# Friedman_BeOd.net
KiCad netlist of a schematic drawn in EAGLE
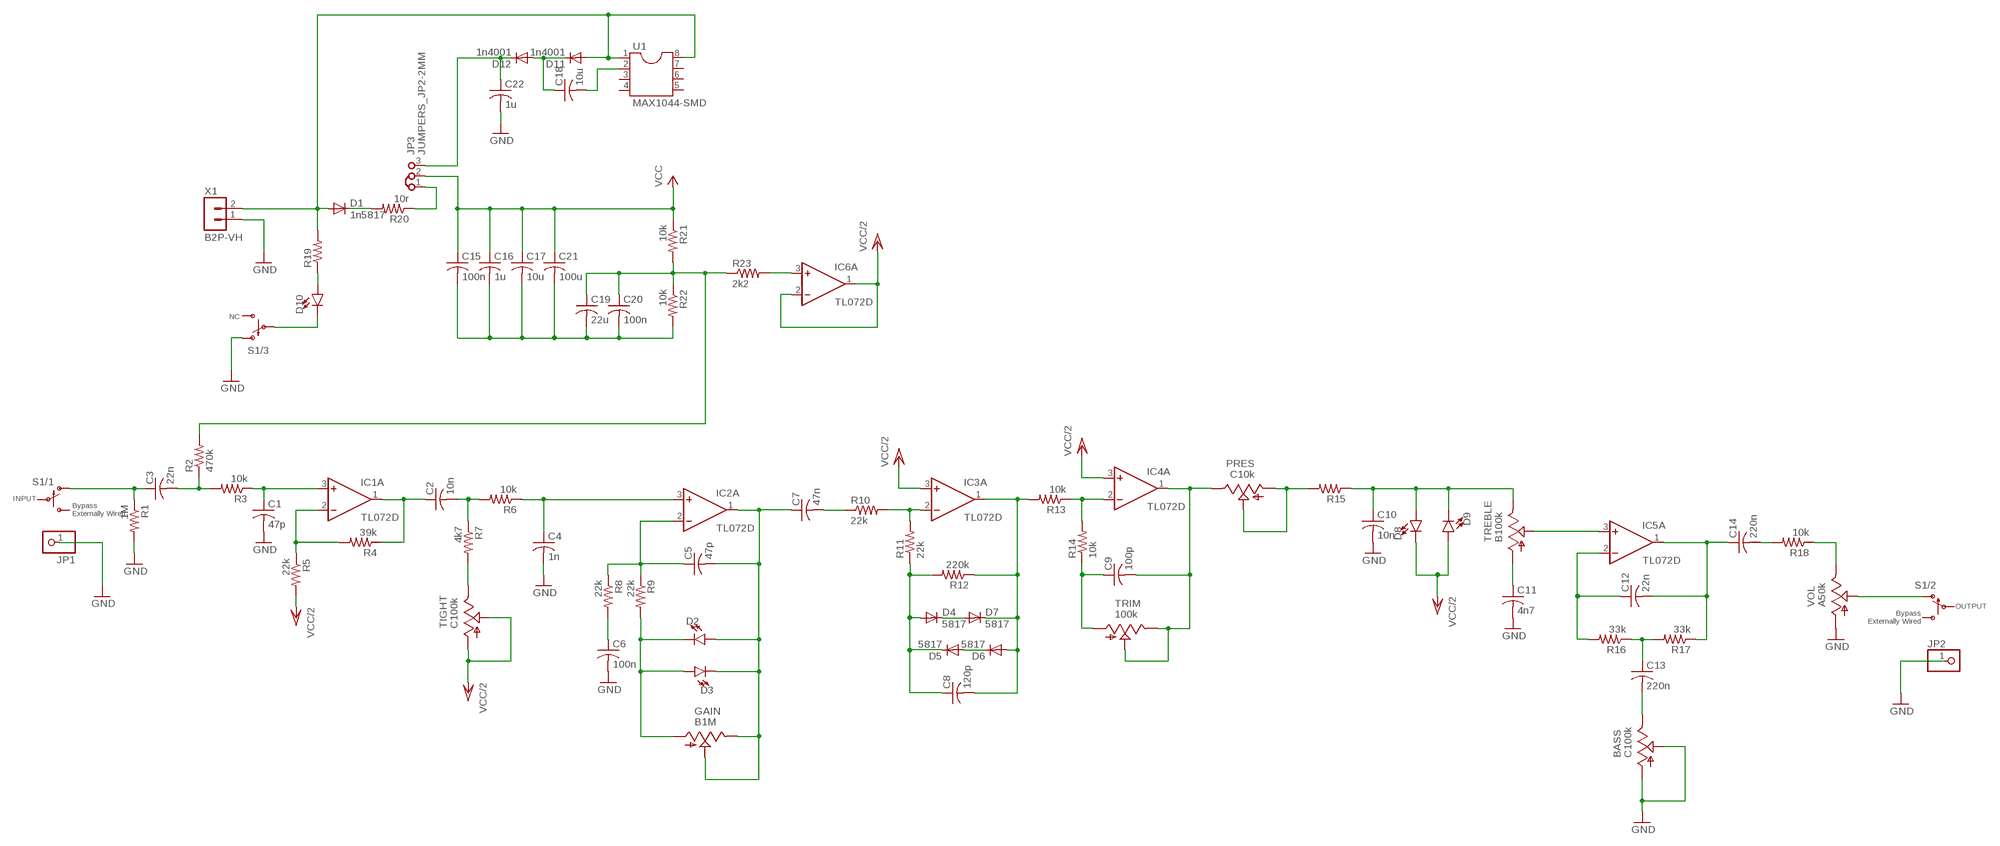
[diagram p0: schematic, sheet 1]

(export (version "E")
  (design (tool "Eeschema 10.0.6"))
  (components
    (comp (ref "BASS")
      (value "C100k")
      (footprint "eagle-import:61300311121")
      (libsource (lib "eagle-import") (part "POT"))
    )
    (comp (ref "C1")
      (value "47p")
      (footprint "eagle-import:C0603")
      (libsource (lib "eagle-import") (part "C-USC0603"))
    )
    (comp (ref "C2")
      (value "10n")
      (footprint "eagle-import:C0603")
      (libsource (lib "eagle-import") (part "C-USC0603"))
    )
    (comp (ref "C3")
      (value "22n")
      (footprint "eagle-import:C0603")
      (libsource (lib "eagle-import") (part "C-USC0603"))
    )
    (comp (ref "C4")
      (value "1n")
      (footprint "eagle-import:C0603")
      (libsource (lib "eagle-import") (part "C-USC0603"))
    )
    (comp (ref "C5")
      (value "47p")
      (footprint "eagle-import:C0603")
      (libsource (lib "eagle-import") (part "C-USC0603"))
    )
    (comp (ref "C6")
      (value "100n")
      (footprint "eagle-import:C0603")
      (libsource (lib "eagle-import") (part "C-USC0603"))
    )
    (comp (ref "C7")
      (value "47n")
      (footprint "eagle-import:C0603")
      (libsource (lib "eagle-import") (part "C-USC0603"))
    )
    (comp (ref "C8")
      (value "120p")
      (footprint "eagle-import:C0603")
      (libsource (lib "eagle-import") (part "C-USC0603"))
    )
    (comp (ref "C9")
      (value "100p")
      (footprint "eagle-import:C0603")
      (libsource (lib "eagle-import") (part "C-USC0603"))
    )
    (comp (ref "C10")
      (value "10n")
      (footprint "eagle-import:C0603")
      (libsource (lib "eagle-import") (part "C-USC0603"))
    )
    (comp (ref "C11")
      (value "4n7")
      (footprint "eagle-import:C0603")
      (libsource (lib "eagle-import") (part "C-USC0603"))
    )
    (comp (ref "C12")
      (value "22n")
      (footprint "eagle-import:C0603")
      (libsource (lib "eagle-import") (part "C-USC0603"))
    )
    (comp (ref "C13")
      (value "220n")
      (footprint "eagle-import:C0603")
      (libsource (lib "eagle-import") (part "C-USC0603"))
    )
    (comp (ref "C14")
      (value "220n")
      (footprint "eagle-import:C0603")
      (libsource (lib "eagle-import") (part "C-USC0603"))
    )
    (comp (ref "C15")
      (value "100n")
      (footprint "eagle-import:C0603")
      (libsource (lib "eagle-import") (part "C-USC0603"))
    )
    (comp (ref "C16")
      (value "1u")
      (footprint "eagle-import:C0603")
      (libsource (lib "eagle-import") (part "C-USC0603"))
    )
    (comp (ref "C17")
      (value "10u")
      (footprint "eagle-import:C0603")
      (libsource (lib "eagle-import") (part "C-USC0603"))
    )
    (comp (ref "C18")
      (value "10u")
      (footprint "eagle-import:C0603")
      (libsource (lib "eagle-import") (part "C-USC0603"))
    )
    (comp (ref "C19")
      (value "22u")
      (footprint "eagle-import:C0603")
      (libsource (lib "eagle-import") (part "C-USC0603"))
    )
    (comp (ref "C20")
      (value "100n")
      (footprint "eagle-import:C0603")
      (libsource (lib "eagle-import") (part "C-USC0603"))
    )
    (comp (ref "C21")
      (value "100u")
      (footprint "eagle-import:C075-032X103")
      (libsource (lib "eagle-import") (part "C-US075-032X103"))
    )
    (comp (ref "C22")
      (value "1u")
      (footprint "eagle-import:C0603")
      (libsource (lib "eagle-import") (part "C-USC0603"))
    )
    (comp (ref "D1")
      (value "1n5817")
      (footprint "eagle-import:DO41-10")
      (libsource (lib "eagle-import") (part "1N4004"))
    )
    (comp (ref "D2")
      (value "LED3MM")
      (footprint "eagle-import:LED_3MM")
      (libsource (lib "eagle-import") (part "LED3MM"))
    )
    (comp (ref "D3")
      (value "LED3MM")
      (footprint "eagle-import:LED_3MM")
      (libsource (lib "eagle-import") (part "LED3MM"))
    )
    (comp (ref "D4")
      (value "5817")
      (footprint "eagle-import:DO41-10")
      (libsource (lib "eagle-import") (part "1N4004"))
    )
    (comp (ref "D5")
      (value "5817")
      (footprint "eagle-import:DO41-10")
      (libsource (lib "eagle-import") (part "1N4004"))
    )
    (comp (ref "D6")
      (value "5817")
      (footprint "eagle-import:DO41-10")
      (libsource (lib "eagle-import") (part "1N4004"))
    )
    (comp (ref "D7")
      (value "5817")
      (footprint "eagle-import:DO41-10")
      (libsource (lib "eagle-import") (part "1N4004"))
    )
    (comp (ref "D8")
      (value "LED3MM")
      (footprint "eagle-import:LED_3MM")
      (libsource (lib "eagle-import") (part "LED3MM"))
    )
    (comp (ref "D9")
      (value "LED3MM")
      (footprint "eagle-import:LED_3MM")
      (libsource (lib "eagle-import") (part "LED3MM"))
    )
    (comp (ref "D10")
      (value "LED3MM")
      (footprint "eagle-import:LED_3MM")
      (libsource (lib "eagle-import") (part "LED3MM"))
    )
    (comp (ref "D11")
      (value "1n4001")
      (footprint "eagle-import:DO41-10")
      (libsource (lib "eagle-import") (part "1N4004"))
    )
    (comp (ref "D12")
      (value "1n4001")
      (footprint "eagle-import:DO41-10")
      (libsource (lib "eagle-import") (part "1N4004"))
    )
    (comp (ref "GAIN")
      (value "B1M")
      (footprint "eagle-import:61300311121")
      (libsource (lib "eagle-import") (part "POT"))
    )
    (comp (ref "IC1")
      (value "TL072D")
      (footprint "eagle-import:SO08")
      (libsource (lib "eagle-import") (part "TL072D"))
    )
    (comp (ref "IC2")
      (value "TL072D")
      (footprint "eagle-import:SO08")
      (libsource (lib "eagle-import") (part "TL072D"))
    )
    (comp (ref "IC3")
      (value "TL072D")
      (footprint "eagle-import:SO08")
      (libsource (lib "eagle-import") (part "TL072D"))
    )
    (comp (ref "IC4")
      (value "TL072D")
      (footprint "eagle-import:SO08")
      (libsource (lib "eagle-import") (part "TL072D"))
    )
    (comp (ref "IC5")
      (value "TL072D")
      (footprint "eagle-import:SO08")
      (libsource (lib "eagle-import") (part "TL072D"))
    )
    (comp (ref "IC6")
      (value "TL072D")
      (footprint "eagle-import:SO08")
      (libsource (lib "eagle-import") (part "TL072D"))
    )
    (comp (ref "JP1")
      (value "PINHD-1X1")
      (footprint "eagle-import:1X01")
      (libsource (lib "eagle-import") (part "PINHD-1X1"))
    )
    (comp (ref "JP2")
      (value "PINHD-1X1")
      (footprint "eagle-import:1X01")
      (libsource (lib "eagle-import") (part "PINHD-1X1"))
    )
    (comp (ref "JP3")
      (value "JUMPERS_JP2-2MM")
      (footprint "eagle-import:JUMPERS_JP2-2MM")
      (libsource (lib "eagle-import") (part "JUMPERS_JP2-2MM"))
    )
    (comp (ref "PRES")
      (value "C10k")
      (footprint "eagle-import:61300311121")
      (libsource (lib "eagle-import") (part "POT"))
    )
    (comp (ref "R1")
      (value "1M")
      (footprint "eagle-import:R0603")
      (libsource (lib "eagle-import") (part "R-US_R0603"))
    )
    (comp (ref "R2")
      (value "470k")
      (footprint "eagle-import:R0603")
      (libsource (lib "eagle-import") (part "R-US_R0603"))
    )
    (comp (ref "R3")
      (value "10k")
      (footprint "eagle-import:R0603")
      (libsource (lib "eagle-import") (part "R-US_R0603"))
    )
    (comp (ref "R4")
      (value "39k")
      (footprint "eagle-import:R0603")
      (libsource (lib "eagle-import") (part "R-US_R0603"))
    )
    (comp (ref "R5")
      (value "22k")
      (footprint "eagle-import:R0603")
      (libsource (lib "eagle-import") (part "R-US_R0603"))
    )
    (comp (ref "R6")
      (value "10k")
      (footprint "eagle-import:R0603")
      (libsource (lib "eagle-import") (part "R-US_R0603"))
    )
    (comp (ref "R7")
      (value "4k7")
      (footprint "eagle-import:R0603")
      (libsource (lib "eagle-import") (part "R-US_R0603"))
    )
    (comp (ref "R8")
      (value "22k")
      (footprint "eagle-import:R0603")
      (libsource (lib "eagle-import") (part "R-US_R0603"))
    )
    (comp (ref "R9")
      (value "22k")
      (footprint "eagle-import:R0603")
      (libsource (lib "eagle-import") (part "R-US_R0603"))
    )
    (comp (ref "R10")
      (value "22k")
      (footprint "eagle-import:R0603")
      (libsource (lib "eagle-import") (part "R-US_R0603"))
    )
    (comp (ref "R11")
      (value "22k")
      (footprint "eagle-import:R0603")
      (libsource (lib "eagle-import") (part "R-US_R0603"))
    )
    (comp (ref "R12")
      (value "220k")
      (footprint "eagle-import:R0603")
      (libsource (lib "eagle-import") (part "R-US_R0603"))
    )
    (comp (ref "R13")
      (value "10k")
      (footprint "eagle-import:R0603")
      (libsource (lib "eagle-import") (part "R-US_R0603"))
    )
    (comp (ref "R14")
      (value "10k")
      (footprint "eagle-import:R0603")
      (libsource (lib "eagle-import") (part "R-US_R0603"))
    )
    (comp (ref "R15")
      (value "R-US_R0603")
      (footprint "eagle-import:R0603")
      (libsource (lib "eagle-import") (part "R-US_R0603"))
    )
    (comp (ref "R16")
      (value "33k")
      (footprint "eagle-import:R0603")
      (libsource (lib "eagle-import") (part "R-US_R0603"))
    )
    (comp (ref "R17")
      (value "33k")
      (footprint "eagle-import:R0603")
      (libsource (lib "eagle-import") (part "R-US_R0603"))
    )
    (comp (ref "R18")
      (value "10k")
      (footprint "eagle-import:R0603")
      (libsource (lib "eagle-import") (part "R-US_R0603"))
    )
    (comp (ref "R19")
      (value "R-US_R0603")
      (footprint "eagle-import:R0603")
      (libsource (lib "eagle-import") (part "R-US_R0603"))
    )
    (comp (ref "R20")
      (value "10r")
      (footprint "eagle-import:R0603")
      (libsource (lib "eagle-import") (part "R-US_R0603"))
    )
    (comp (ref "R21")
      (value "10k")
      (footprint "eagle-import:R0603")
      (libsource (lib "eagle-import") (part "R-US_R0603"))
    )
    (comp (ref "R22")
      (value "10k")
      (footprint "eagle-import:R0603")
      (libsource (lib "eagle-import") (part "R-US_R0603"))
    )
    (comp (ref "R23")
      (value "2k2")
      (footprint "eagle-import:R0603")
      (libsource (lib "eagle-import") (part "R-US_R0603"))
    )
    (comp (ref "S1")
      (value "SWITCH-3DPT-INLINE-BREAKOUT-BYPASS")
      (footprint "eagle-import:1X04")
      (libsource (lib "eagle-import") (part "SWITCH-3DPT-INLINE-BREAKOUT-BYPASS"))
    )
    (comp (ref "TIGHT")
      (value "C100k")
      (footprint "eagle-import:61300311121")
      (libsource (lib "eagle-import") (part "POT"))
    )
    (comp (ref "TREBLE")
      (value "B100k")
      (footprint "eagle-import:61300311121")
      (libsource (lib "eagle-import") (part "POT"))
    )
    (comp (ref "TRIM")
      (value "100k")
      (footprint "eagle-import:61300311121")
      (libsource (lib "eagle-import") (part "POT"))
    )
    (comp (ref "U1")
      (value "MAX1044-SMD")
      (footprint "eagle-import:SO-08")
      (libsource (lib "eagle-import") (part "MAX1044-SMD"))
    )
    (comp (ref "VOL")
      (value "A50k")
      (footprint "eagle-import:61300311121")
      (libsource (lib "eagle-import") (part "POT"))
    )
    (comp (ref "X1")
      (value "B2P-VH")
      (footprint "eagle-import:B2P-VH")
      (libsource (lib "eagle-import") (part "B2P-VH"))
    )
  )
  (nets
    (net (code "1") (name "GND") (class "Default")
      (node (ref "BASS") (pin "1") (pinfunction "LEFT_1") (pintype "passive"))
      (node (ref "BASS") (pin "2") (pinfunction "WIPER_2") (pintype "passive"))
      (node (ref "C1") (pin "2") (pinfunction "2_2") (pintype "passive"))
      (node (ref "C10") (pin "2") (pinfunction "2_2") (pintype "passive"))
      (node (ref "C11") (pin "2") (pinfunction "2_2") (pintype "passive"))
      (node (ref "C22") (pin "2") (pinfunction "2_2") (pintype "passive"))
      (node (ref "C4") (pin "2") (pinfunction "2_2") (pintype "passive"))
      (node (ref "C6") (pin "2") (pinfunction "2_2") (pintype "passive"))
      (node (ref "JP1") (pin "1") (pinfunction "1_1") (pintype "passive"))
      (node (ref "JP2") (pin "1") (pinfunction "1_1") (pintype "passive"))
      (node (ref "R1") (pin "2") (pinfunction "2_2") (pintype "passive"))
      (node (ref "S1") (pin "4") (pinfunction "NORMALLY-ON_4") (pintype "passive"))
      (node (ref "VOL") (pin "1") (pinfunction "LEFT_1") (pintype "passive"))
      (node (ref "X1") (pin "1") (pinfunction "1_1") (pintype "passive"))
    )
    (net (code "2") (name "Net-(BASS-RIGHT)") (class "Default")
      (node (ref "BASS") (pin "3") (pinfunction "RIGHT_3") (pintype "passive"))
      (node (ref "C13") (pin "2") (pinfunction "2_2") (pintype "passive"))
    )
    (net (code "3") (name "Net-(C2-Pad2)") (class "Default")
      (node (ref "C2") (pin "2") (pinfunction "2_2") (pintype "passive"))
      (node (ref "R6") (pin "2") (pinfunction "2_2") (pintype "passive"))
      (node (ref "R7") (pin "1") (pinfunction "1_1") (pintype "passive"))
    )
    (net (code "4") (name "Net-(C3-Pad2)") (class "Default")
      (node (ref "C3") (pin "2") (pinfunction "2_2") (pintype "passive"))
      (node (ref "R2") (pin "1") (pinfunction "1_1") (pintype "passive"))
      (node (ref "R3") (pin "2") (pinfunction "2_2") (pintype "passive"))
    )
    (net (code "5") (name "Net-(C6-Pad1)") (class "Default")
      (node (ref "C6") (pin "1") (pinfunction "1_1") (pintype "passive"))
      (node (ref "R8") (pin "2") (pinfunction "2_2") (pintype "passive"))
    )
    (net (code "6") (name "Net-(C7-Pad2)") (class "Default")
      (node (ref "C7") (pin "2") (pinfunction "2_2") (pintype "passive"))
      (node (ref "R10") (pin "1") (pinfunction "1_1") (pintype "passive"))
    )
    (net (code "7") (name "Net-(C8-Pad1)") (class "Default")
      (node (ref "C8") (pin "1") (pinfunction "1_1") (pintype "passive"))
      (node (ref "D4") (pin "A") (pinfunction "A_A") (pintype "passive"))
      (node (ref "D5") (pin "C") (pinfunction "C_C") (pintype "passive"))
      (node (ref "R11") (pin "1") (pinfunction "1_1") (pintype "passive"))
      (node (ref "R12") (pin "2") (pinfunction "2_2") (pintype "passive"))
    )
    (net (code "8") (name "Net-(C13-Pad1)") (class "Default")
      (node (ref "C13") (pin "1") (pinfunction "1_1") (pintype "passive"))
      (node (ref "R16") (pin "1") (pinfunction "1_1") (pintype "passive"))
      (node (ref "R17") (pin "2") (pinfunction "2_2") (pintype "passive"))
    )
    (net (code "9") (name "Net-(C14-Pad2)") (class "Default")
      (node (ref "C14") (pin "2") (pinfunction "2_2") (pintype "passive"))
      (node (ref "R18") (pin "2") (pinfunction "2_2") (pintype "passive"))
    )
    (net (code "10") (name "Net-(C15-Pad2)") (class "Default")
      (node (ref "C15") (pin "2") (pinfunction "2_2") (pintype "passive"))
      (node (ref "C16") (pin "2") (pinfunction "2_2") (pintype "passive"))
      (node (ref "C17") (pin "2") (pinfunction "2_2") (pintype "passive"))
      (node (ref "C19") (pin "2") (pinfunction "2_2") (pintype "passive"))
      (node (ref "C20") (pin "2") (pinfunction "2_2") (pintype "passive"))
      (node (ref "C21") (pin "2") (pinfunction "2_2") (pintype "passive"))
      (node (ref "R22") (pin "2") (pinfunction "2_2") (pintype "passive"))
    )
    (net (code "11") (name "Net-(C18-Pad1)") (class "Default")
      (node (ref "C18") (pin "1") (pinfunction "1_1") (pintype "passive"))
      (node (ref "D11") (pin "C") (pinfunction "C_C") (pintype "passive"))
      (node (ref "D12") (pin "A") (pinfunction "A_A") (pintype "passive"))
    )
    (net (code "12") (name "Net-(C18-Pad2)") (class "Default")
      (node (ref "C18") (pin "2") (pinfunction "2_2") (pintype "passive"))
      (node (ref "U1") (pin "2") (pinfunction "2_2") (pintype "passive"))
    )
    (net (code "13") (name "Net-(C19-Pad1)") (class "Default")
      (node (ref "C19") (pin "1") (pinfunction "1_1") (pintype "passive"))
      (node (ref "C20") (pin "1") (pinfunction "1_1") (pintype "passive"))
      (node (ref "R2") (pin "2") (pinfunction "2_2") (pintype "passive"))
      (node (ref "R21") (pin "2") (pinfunction "2_2") (pintype "passive"))
      (node (ref "R22") (pin "1") (pinfunction "1_1") (pintype "passive"))
      (node (ref "R23") (pin "1") (pinfunction "1_1") (pintype "passive"))
    )
    (net (code "14") (name "Net-(C22-Pad1)") (class "Default")
      (node (ref "C22") (pin "1") (pinfunction "1_1") (pintype "passive"))
      (node (ref "D12") (pin "C") (pinfunction "C_C") (pintype "passive"))
      (node (ref "JP3") (pin "3") (pinfunction "3_3") (pintype "passive"))
    )
    (net (code "15") (name "Net-(D1-PadA)") (class "Default")
      (node (ref "D1") (pin "A") (pinfunction "A_A") (pintype "passive"))
      (node (ref "D11") (pin "A") (pinfunction "A_A") (pintype "passive"))
      (node (ref "R19") (pin "2") (pinfunction "2_2") (pintype "passive"))
      (node (ref "U1") (pin "1") (pinfunction "1_1") (pintype "passive"))
      (node (ref "U1") (pin "8") (pinfunction "8_8") (pintype "passive"))
      (node (ref "X1") (pin "2") (pinfunction "2_2") (pintype "passive"))
    )
    (net (code "16") (name "Net-(D1-PadC)") (class "Default")
      (node (ref "D1") (pin "C") (pinfunction "C_C") (pintype "passive"))
      (node (ref "R20") (pin "2") (pinfunction "2_2") (pintype "passive"))
    )
    (net (code "17") (name "Net-(D2-C)") (class "Default")
      (node (ref "D2") (pin "K") (pinfunction "C_K") (pintype "passive"))
      (node (ref "D3") (pin "A") (pinfunction "A_A") (pintype "passive"))
      (node (ref "GAIN") (pin "1") (pinfunction "LEFT_1") (pintype "passive"))
      (node (ref "R9") (pin "2") (pinfunction "2_2") (pintype "passive"))
    )
    (net (code "18") (name "Net-(D3-C)") (class "Default")
      (node (ref "C5") (pin "2") (pinfunction "2_2") (pintype "passive"))
      (node (ref "C7") (pin "1") (pinfunction "1_1") (pintype "passive"))
      (node (ref "D2") (pin "A") (pinfunction "A_A") (pintype "passive"))
      (node (ref "D3") (pin "K") (pinfunction "C_K") (pintype "passive"))
      (node (ref "GAIN") (pin "2") (pinfunction "WIPER_2") (pintype "passive"))
      (node (ref "GAIN") (pin "3") (pinfunction "RIGHT_3") (pintype "passive"))
      (node (ref "IC2") (pin "1") (pinfunction "OUT_1") (pintype "output"))
    )
    (net (code "19") (name "Net-(D4-PadC)") (class "Default")
      (node (ref "D4") (pin "C") (pinfunction "C_C") (pintype "passive"))
      (node (ref "D7") (pin "A") (pinfunction "A_A") (pintype "passive"))
    )
    (net (code "20") (name "Net-(D5-PadA)") (class "Default")
      (node (ref "D5") (pin "A") (pinfunction "A_A") (pintype "passive"))
      (node (ref "D6") (pin "C") (pinfunction "C_C") (pintype "passive"))
    )
    (net (code "21") (name "Net-(D9-C)") (class "Default")
      (node (ref "C10") (pin "1") (pinfunction "1_1") (pintype "passive"))
      (node (ref "D8") (pin "A") (pinfunction "A_A") (pintype "passive"))
      (node (ref "D9") (pin "K") (pinfunction "C_K") (pintype "passive"))
      (node (ref "R15") (pin "1") (pinfunction "1_1") (pintype "passive"))
      (node (ref "TREBLE") (pin "3") (pinfunction "RIGHT_3") (pintype "passive"))
    )
    (net (code "22") (name "Net-(D10-C)") (class "Default")
      (node (ref "D10") (pin "K") (pinfunction "C_K") (pintype "passive"))
      (node (ref "S1") (pin "3") (pinfunction "COMMON_3") (pintype "passive"))
    )
    (net (code "23") (name "Net-(D10-PadA)") (class "Default")
      (node (ref "D10") (pin "A") (pinfunction "A_A") (pintype "passive"))
      (node (ref "R19") (pin "1") (pinfunction "1_1") (pintype "passive"))
    )
    (net (code "24") (name "Net-(IC1A-+IN)") (class "Default")
      (node (ref "C1") (pin "1") (pinfunction "1_1") (pintype "passive"))
      (node (ref "IC1") (pin "3") (pinfunction "+IN_3") (pintype "input"))
      (node (ref "R3") (pin "1") (pinfunction "1_1") (pintype "passive"))
    )
    (net (code "25") (name "Net-(IC1A--IN)") (class "Default")
      (node (ref "IC1") (pin "2") (pinfunction "-IN_2") (pintype "input"))
      (node (ref "R4") (pin "2") (pinfunction "2_2") (pintype "passive"))
      (node (ref "R5") (pin "1") (pinfunction "1_1") (pintype "passive"))
    )
    (net (code "26") (name "Net-(IC1A-OUT)") (class "Default")
      (node (ref "C2") (pin "1") (pinfunction "1_1") (pintype "passive"))
      (node (ref "IC1") (pin "1") (pinfunction "OUT_1") (pintype "output"))
      (node (ref "R4") (pin "1") (pinfunction "1_1") (pintype "passive"))
    )
    (net (code "27") (name "Net-(IC2A-+IN)") (class "Default")
      (node (ref "C4") (pin "1") (pinfunction "1_1") (pintype "passive"))
      (node (ref "IC2") (pin "3") (pinfunction "+IN_3") (pintype "input"))
      (node (ref "R6") (pin "1") (pinfunction "1_1") (pintype "passive"))
    )
    (net (code "28") (name "Net-(IC2A--IN)") (class "Default")
      (node (ref "C5") (pin "1") (pinfunction "1_1") (pintype "passive"))
      (node (ref "IC2") (pin "2") (pinfunction "-IN_2") (pintype "input"))
      (node (ref "R8") (pin "1") (pinfunction "1_1") (pintype "passive"))
      (node (ref "R9") (pin "1") (pinfunction "1_1") (pintype "passive"))
    )
    (net (code "29") (name "Net-(IC3A--IN)") (class "Default")
      (node (ref "IC3") (pin "2") (pinfunction "-IN_2") (pintype "input"))
      (node (ref "R10") (pin "2") (pinfunction "2_2") (pintype "passive"))
      (node (ref "R11") (pin "2") (pinfunction "2_2") (pintype "passive"))
    )
    (net (code "30") (name "Net-(IC3A-OUT)") (class "Default")
      (node (ref "C8") (pin "2") (pinfunction "2_2") (pintype "passive"))
      (node (ref "D6") (pin "A") (pinfunction "A_A") (pintype "passive"))
      (node (ref "D7") (pin "C") (pinfunction "C_C") (pintype "passive"))
      (node (ref "IC3") (pin "1") (pinfunction "OUT_1") (pintype "output"))
      (node (ref "R12") (pin "1") (pinfunction "1_1") (pintype "passive"))
      (node (ref "R13") (pin "2") (pinfunction "2_2") (pintype "passive"))
    )
    (net (code "31") (name "Net-(IC4A--IN)") (class "Default")
      (node (ref "IC4") (pin "2") (pinfunction "-IN_2") (pintype "input"))
      (node (ref "R13") (pin "1") (pinfunction "1_1") (pintype "passive"))
      (node (ref "R14") (pin "2") (pinfunction "2_2") (pintype "passive"))
    )
    (net (code "32") (name "Net-(IC4A-OUT)") (class "Default")
      (node (ref "C9") (pin "2") (pinfunction "2_2") (pintype "passive"))
      (node (ref "IC4") (pin "1") (pinfunction "OUT_1") (pintype "output"))
      (node (ref "PRES") (pin "3") (pinfunction "RIGHT_3") (pintype "passive"))
      (node (ref "TRIM") (pin "2") (pinfunction "WIPER_2") (pintype "passive"))
      (node (ref "TRIM") (pin "3") (pinfunction "RIGHT_3") (pintype "passive"))
    )
    (net (code "33") (name "Net-(IC5A-+IN)") (class "Default")
      (node (ref "IC5") (pin "3") (pinfunction "+IN_3") (pintype "input"))
      (node (ref "TREBLE") (pin "2") (pinfunction "WIPER_2") (pintype "passive"))
    )
    (net (code "34") (name "Net-(IC5A--IN)") (class "Default")
      (node (ref "C12") (pin "1") (pinfunction "1_1") (pintype "passive"))
      (node (ref "IC5") (pin "2") (pinfunction "-IN_2") (pintype "input"))
      (node (ref "R16") (pin "2") (pinfunction "2_2") (pintype "passive"))
    )
    (net (code "35") (name "Net-(IC5A-OUT)") (class "Default")
      (node (ref "C12") (pin "2") (pinfunction "2_2") (pintype "passive"))
      (node (ref "C14") (pin "1") (pinfunction "1_1") (pintype "passive"))
      (node (ref "IC5") (pin "1") (pinfunction "OUT_1") (pintype "output"))
      (node (ref "R17") (pin "1") (pinfunction "1_1") (pintype "passive"))
    )
    (net (code "36") (name "Net-(IC6A-+IN)") (class "Default")
      (node (ref "IC6") (pin "3") (pinfunction "+IN_3") (pintype "input"))
      (node (ref "R23") (pin "2") (pinfunction "2_2") (pintype "passive"))
    )
    (net (code "37") (name "Net-(JP3-Pad1)") (class "Default")
      (node (ref "JP3") (pin "1") (pinfunction "1_1") (pintype "passive"))
      (node (ref "R20") (pin "1") (pinfunction "1_1") (pintype "passive"))
    )
    (net (code "38") (name "Net-(PRES-LEFT)") (class "Default")
      (node (ref "PRES") (pin "1") (pinfunction "LEFT_1") (pintype "passive"))
      (node (ref "PRES") (pin "2") (pinfunction "WIPER_2") (pintype "passive"))
      (node (ref "R15") (pin "2") (pinfunction "2_2") (pintype "passive"))
    )
    (net (code "39") (name "Net-(S1A-NORMALLY-ON)") (class "Default")
      (node (ref "C3") (pin "1") (pinfunction "1_1") (pintype "passive"))
      (node (ref "R1") (pin "1") (pinfunction "1_1") (pintype "passive"))
      (node (ref "S1") (pin "1") (pinfunction "NORMALLY-ON_1") (pintype "passive"))
    )
    (net (code "40") (name "Net-(S1B-NORMALLY-ON)") (class "Default")
      (node (ref "S1") (pin "2") (pinfunction "NORMALLY-ON_2") (pintype "passive"))
      (node (ref "VOL") (pin "2") (pinfunction "WIPER_2") (pintype "passive"))
    )
    (net (code "41") (name "Net-(TIGHT-RIGHT)") (class "Default")
      (node (ref "R7") (pin "2") (pinfunction "2_2") (pintype "passive"))
      (node (ref "TIGHT") (pin "3") (pinfunction "RIGHT_3") (pintype "passive"))
    )
    (net (code "42") (name "Net-(TREBLE-LEFT)") (class "Default")
      (node (ref "C11") (pin "1") (pinfunction "1_1") (pintype "passive"))
      (node (ref "TREBLE") (pin "1") (pinfunction "LEFT_1") (pintype "passive"))
    )
    (net (code "43") (name "Net-(TRIM-LEFT)") (class "Default")
      (node (ref "C9") (pin "1") (pinfunction "1_1") (pintype "passive"))
      (node (ref "R14") (pin "1") (pinfunction "1_1") (pintype "passive"))
      (node (ref "TRIM") (pin "1") (pinfunction "LEFT_1") (pintype "passive"))
    )
    (net (code "44") (name "Net-(VOL-RIGHT)") (class "Default")
      (node (ref "R18") (pin "1") (pinfunction "1_1") (pintype "passive"))
      (node (ref "VOL") (pin "3") (pinfunction "RIGHT_3") (pintype "passive"))
    )
    (net (code "45") (name "VCC") (class "Default")
      (node (ref "C15") (pin "1") (pinfunction "1_1") (pintype "passive"))
      (node (ref "C16") (pin "1") (pinfunction "1_1") (pintype "passive"))
      (node (ref "C17") (pin "1") (pinfunction "1_1") (pintype "passive"))
      (node (ref "C21") (pin "1") (pinfunction "1_1") (pintype "passive"))
      (node (ref "JP3") (pin "2") (pinfunction "2_2") (pintype "passive"))
      (node (ref "R21") (pin "1") (pinfunction "1_1") (pintype "passive"))
    )
    (net (code "46") (name "VCC{slash}2") (class "Default")
      (node (ref "D8") (pin "K") (pinfunction "C_K") (pintype "passive"))
      (node (ref "D9") (pin "A") (pinfunction "A_A") (pintype "passive"))
      (node (ref "IC3") (pin "3") (pinfunction "+IN_3") (pintype "input"))
      (node (ref "IC4") (pin "3") (pinfunction "+IN_3") (pintype "input"))
      (node (ref "IC6") (pin "1") (pinfunction "OUT_1") (pintype "output"))
      (node (ref "IC6") (pin "2") (pinfunction "-IN_2") (pintype "input"))
      (node (ref "R5") (pin "2") (pinfunction "2_2") (pintype "passive"))
      (node (ref "TIGHT") (pin "1") (pinfunction "LEFT_1") (pintype "passive"))
      (node (ref "TIGHT") (pin "2") (pinfunction "WIPER_2") (pintype "passive"))
    )
    (net (code "47") (name "unconnected-(U1-Pad3)") (class "Default")
      (node (ref "U1") (pin "3") (pinfunction "3_3") (pintype "passive"))
    )
    (net (code "48") (name "unconnected-(U1-Pad4)") (class "Default")
      (node (ref "U1") (pin "4") (pinfunction "4_4") (pintype "passive"))
    )
    (net (code "49") (name "unconnected-(U1-Pad5)") (class "Default")
      (node (ref "U1") (pin "5") (pinfunction "5_5") (pintype "passive"))
    )
    (net (code "50") (name "unconnected-(U1-Pad6)") (class "Default")
      (node (ref "U1") (pin "6") (pinfunction "6_6") (pintype "passive"))
    )
    (net (code "51") (name "unconnected-(U1-Pad7)") (class "Default")
      (node (ref "U1") (pin "7") (pinfunction "7_7") (pintype "passive"))
    )
  )
)
